# Sheet3.net
KiCad netlist of a schematic drawn in Altium Designer
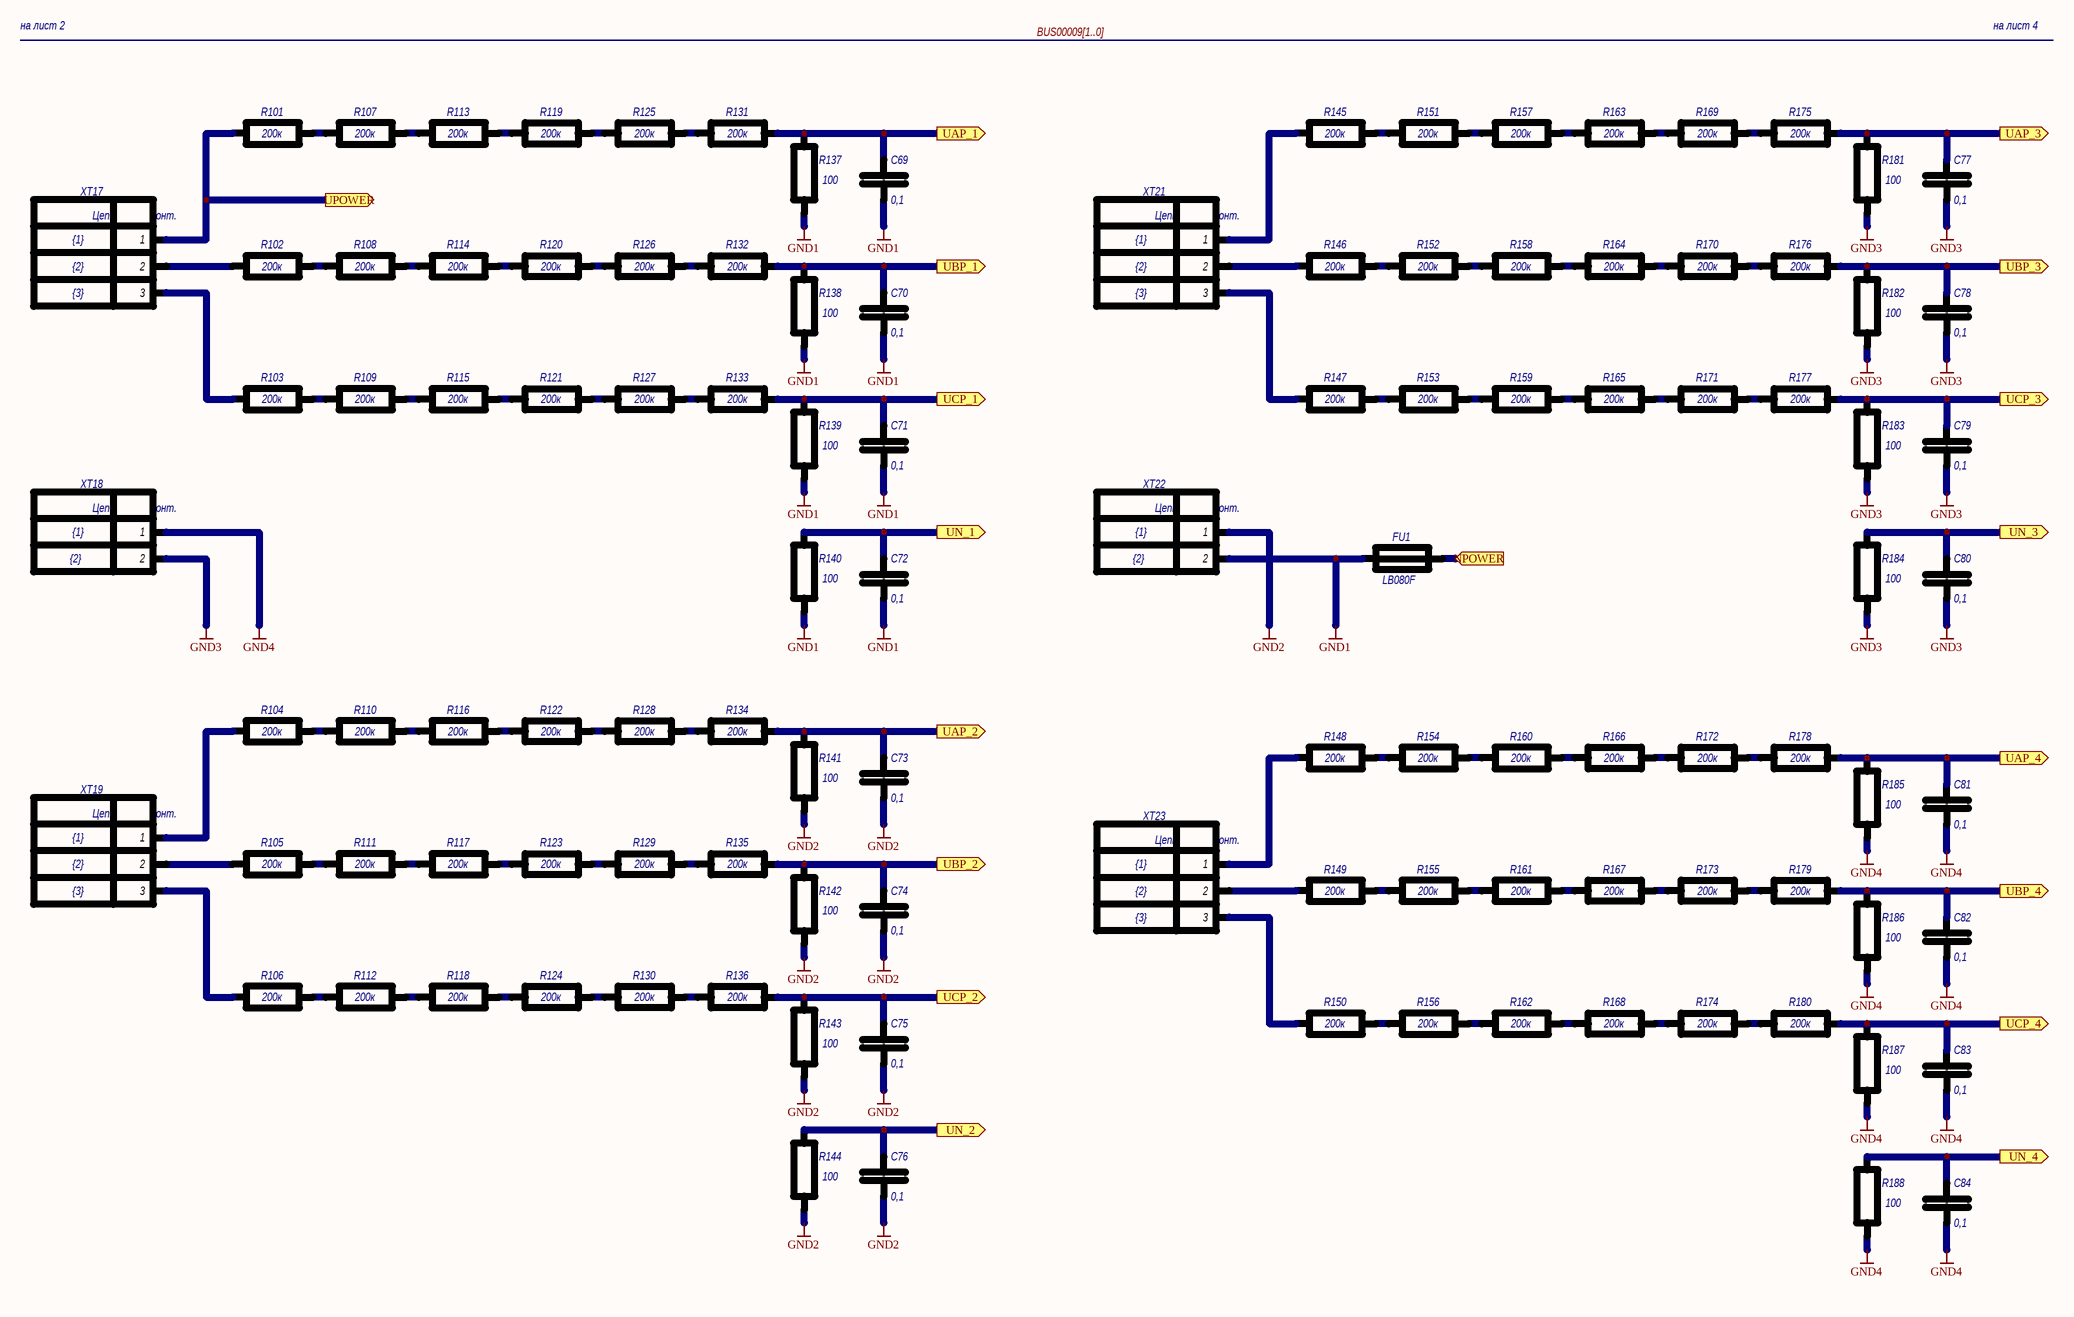
[diagram p0: Sheet3.SCHDOC]

(export (version "E")
  (design (tool "Eeschema 10.0.6"))
  (components
    (comp (ref "C69")
      (value "0,1")
      (footprint "0805")
      (description "КОНДЕНСАТОР")
      (fields (field (name "Comment") "К0805"))
      (libsource (lib "") (part "К0805_1"))
    )
    (comp (ref "C70")
      (value "0,1")
      (footprint "0805")
      (description "КОНДЕНСАТОР")
      (fields (field (name "Comment") "К0805"))
      (libsource (lib "*") (part "К0805"))
    )
    (comp (ref "C71")
      (value "0,1")
      (footprint "0805")
      (description "КОНДЕНСАТОР")
      (fields (field (name "Comment") "К0805"))
      (libsource (lib "*") (part "К0805"))
    )
    (comp (ref "C72")
      (value "0,1")
      (footprint "0805")
      (description "КОНДЕНСАТОР")
      (fields (field (name "Comment") "К0805"))
      (libsource (lib "*") (part "К0805"))
    )
    (comp (ref "C73")
      (value "0,1")
      (footprint "0805")
      (description "КОНДЕНСАТОР")
      (fields (field (name "Comment") "К0805"))
      (libsource (lib "*") (part "К0805"))
    )
    (comp (ref "C74")
      (value "0,1")
      (footprint "0805")
      (description "КОНДЕНСАТОР")
      (fields (field (name "Comment") "К0805"))
      (libsource (lib "*") (part "К0805"))
    )
    (comp (ref "C75")
      (value "0,1")
      (footprint "0805")
      (description "КОНДЕНСАТОР")
      (fields (field (name "Comment") "К0805"))
      (libsource (lib "*") (part "К0805"))
    )
    (comp (ref "C76")
      (value "0,1")
      (footprint "0805")
      (description "КОНДЕНСАТОР")
      (fields (field (name "Comment") "К0805"))
      (libsource (lib "*") (part "К0805"))
    )
    (comp (ref "C77")
      (value "0,1")
      (footprint "0805")
      (description "КОНДЕНСАТОР")
      (fields (field (name "Comment") "К0805"))
      (libsource (lib "") (part "К0805_1"))
    )
    (comp (ref "C78")
      (value "0,1")
      (footprint "0805")
      (description "КОНДЕНСАТОР")
      (fields (field (name "Comment") "К0805"))
      (libsource (lib "*") (part "К0805"))
    )
    (comp (ref "C79")
      (value "0,1")
      (footprint "0805")
      (description "КОНДЕНСАТОР")
      (fields (field (name "Comment") "К0805"))
      (libsource (lib "*") (part "К0805"))
    )
    (comp (ref "C80")
      (value "0,1")
      (footprint "0805")
      (description "КОНДЕНСАТОР")
      (fields (field (name "Comment") "К0805"))
      (libsource (lib "*") (part "К0805"))
    )
    (comp (ref "C81")
      (value "0,1")
      (footprint "0805")
      (description "КОНДЕНСАТОР")
      (fields (field (name "Comment") "К0805"))
      (libsource (lib "*") (part "К0805"))
    )
    (comp (ref "C82")
      (value "0,1")
      (footprint "0805")
      (description "КОНДЕНСАТОР")
      (fields (field (name "Comment") "К0805"))
      (libsource (lib "*") (part "К0805"))
    )
    (comp (ref "C83")
      (value "0,1")
      (footprint "0805")
      (description "КОНДЕНСАТОР")
      (fields (field (name "Comment") "К0805"))
      (libsource (lib "*") (part "К0805"))
    )
    (comp (ref "C84")
      (value "0,1")
      (footprint "0805")
      (description "КОНДЕНСАТОР")
      (fields (field (name "Comment") "К0805"))
      (libsource (lib "*") (part "К0805"))
    )
    (comp (ref "FU1")
      (value "LB080F")
      (footprint "LB080F")
      (description "{Description}")
      (libsource (lib "*") (part "LB080F"))
    )
    (comp (ref "R101")
      (value "Р1206")
      (footprint "1206")
      (description "РЕЗИСТОР")
      (fields (field (name "ALTIUM_UNNAMED_1") "200к"))
      (libsource (lib "*") (part "Р1206"))
    )
    (comp (ref "R102")
      (value "Р1206")
      (footprint "1206")
      (description "РЕЗИСТОР")
      (fields (field (name "ALTIUM_UNNAMED_1") "200к"))
      (libsource (lib "*") (part "Р1206"))
    )
    (comp (ref "R103")
      (value "Р1206")
      (footprint "1206")
      (description "РЕЗИСТОР")
      (fields (field (name "ALTIUM_UNNAMED_1") "200к"))
      (libsource (lib "*") (part "Р1206"))
    )
    (comp (ref "R104")
      (value "Р1206")
      (footprint "1206")
      (description "РЕЗИСТОР")
      (fields (field (name "ALTIUM_UNNAMED_1") "200к"))
      (libsource (lib "*") (part "Р1206"))
    )
    (comp (ref "R105")
      (value "Р1206")
      (footprint "1206")
      (description "РЕЗИСТОР")
      (fields (field (name "ALTIUM_UNNAMED_1") "200к"))
      (libsource (lib "*") (part "Р1206"))
    )
    (comp (ref "R106")
      (value "Р1206")
      (footprint "1206")
      (description "РЕЗИСТОР")
      (fields (field (name "ALTIUM_UNNAMED_1") "200к"))
      (libsource (lib "*") (part "Р1206"))
    )
    (comp (ref "R107")
      (value "Р1206")
      (footprint "1206")
      (description "РЕЗИСТОР")
      (fields (field (name "ALTIUM_UNNAMED_1") "200к"))
      (libsource (lib "") (part "Р1206_1"))
    )
    (comp (ref "R108")
      (value "Р1206")
      (footprint "1206")
      (description "РЕЗИСТОР")
      (fields (field (name "ALTIUM_UNNAMED_1") "200к"))
      (libsource (lib "") (part "Р1206_1"))
    )
    (comp (ref "R109")
      (value "Р1206")
      (footprint "1206")
      (description "РЕЗИСТОР")
      (fields (field (name "ALTIUM_UNNAMED_1") "200к"))
      (libsource (lib "") (part "Р1206_1"))
    )
    (comp (ref "R110")
      (value "Р1206")
      (footprint "1206")
      (description "РЕЗИСТОР")
      (fields (field (name "ALTIUM_UNNAMED_1") "200к"))
      (libsource (lib "") (part "Р1206_1"))
    )
    (comp (ref "R111")
      (value "Р1206")
      (footprint "1206")
      (description "РЕЗИСТОР")
      (fields (field (name "ALTIUM_UNNAMED_1") "200к"))
      (libsource (lib "") (part "Р1206_1"))
    )
    (comp (ref "R112")
      (value "Р1206")
      (footprint "1206")
      (description "РЕЗИСТОР")
      (fields (field (name "ALTIUM_UNNAMED_1") "200к"))
      (libsource (lib "") (part "Р1206_1"))
    )
    (comp (ref "R113")
      (value "Р1206")
      (footprint "1206")
      (description "РЕЗИСТОР")
      (fields (field (name "ALTIUM_UNNAMED_1") "200к"))
      (libsource (lib "*") (part "Р1206"))
    )
    (comp (ref "R114")
      (value "Р1206")
      (footprint "1206")
      (description "РЕЗИСТОР")
      (fields (field (name "ALTIUM_UNNAMED_1") "200к"))
      (libsource (lib "*") (part "Р1206"))
    )
    (comp (ref "R115")
      (value "Р1206")
      (footprint "1206")
      (description "РЕЗИСТОР")
      (fields (field (name "ALTIUM_UNNAMED_1") "200к"))
      (libsource (lib "*") (part "Р1206"))
    )
    (comp (ref "R116")
      (value "Р1206")
      (footprint "1206")
      (description "РЕЗИСТОР")
      (fields (field (name "ALTIUM_UNNAMED_1") "200к"))
      (libsource (lib "*") (part "Р1206"))
    )
    (comp (ref "R117")
      (value "Р1206")
      (footprint "1206")
      (description "РЕЗИСТОР")
      (fields (field (name "ALTIUM_UNNAMED_1") "200к"))
      (libsource (lib "*") (part "Р1206"))
    )
    (comp (ref "R118")
      (value "Р1206")
      (footprint "1206")
      (description "РЕЗИСТОР")
      (fields (field (name "ALTIUM_UNNAMED_1") "200к"))
      (libsource (lib "*") (part "Р1206"))
    )
    (comp (ref "R119")
      (value "Р1206")
      (footprint "1206")
      (description "РЕЗИСТОР")
      (fields (field (name "ALTIUM_UNNAMED_1") "200к"))
      (libsource (lib "*") (part "Р1206"))
    )
    (comp (ref "R120")
      (value "Р1206")
      (footprint "1206")
      (description "РЕЗИСТОР")
      (fields (field (name "ALTIUM_UNNAMED_1") "200к"))
      (libsource (lib "*") (part "Р1206"))
    )
    (comp (ref "R121")
      (value "Р1206")
      (footprint "1206")
      (description "РЕЗИСТОР")
      (fields (field (name "ALTIUM_UNNAMED_1") "200к"))
      (libsource (lib "*") (part "Р1206"))
    )
    (comp (ref "R122")
      (value "Р1206")
      (footprint "1206")
      (description "РЕЗИСТОР")
      (fields (field (name "ALTIUM_UNNAMED_1") "200к"))
      (libsource (lib "*") (part "Р1206"))
    )
    (comp (ref "R123")
      (value "Р1206")
      (footprint "1206")
      (description "РЕЗИСТОР")
      (fields (field (name "ALTIUM_UNNAMED_1") "200к"))
      (libsource (lib "*") (part "Р1206"))
    )
    (comp (ref "R124")
      (value "Р1206")
      (footprint "1206")
      (description "РЕЗИСТОР")
      (fields (field (name "ALTIUM_UNNAMED_1") "200к"))
      (libsource (lib "*") (part "Р1206"))
    )
    (comp (ref "R125")
      (value "Р1206")
      (footprint "1206")
      (description "РЕЗИСТОР")
      (fields (field (name "ALTIUM_UNNAMED_1") "200к"))
      (libsource (lib "*") (part "Р1206"))
    )
    (comp (ref "R126")
      (value "Р1206")
      (footprint "1206")
      (description "РЕЗИСТОР")
      (fields (field (name "ALTIUM_UNNAMED_1") "200к"))
      (libsource (lib "*") (part "Р1206"))
    )
    (comp (ref "R127")
      (value "Р1206")
      (footprint "1206")
      (description "РЕЗИСТОР")
      (fields (field (name "ALTIUM_UNNAMED_1") "200к"))
      (libsource (lib "*") (part "Р1206"))
    )
    (comp (ref "R128")
      (value "Р1206")
      (footprint "1206")
      (description "РЕЗИСТОР")
      (fields (field (name "ALTIUM_UNNAMED_1") "200к"))
      (libsource (lib "*") (part "Р1206"))
    )
    (comp (ref "R129")
      (value "Р1206")
      (footprint "1206")
      (description "РЕЗИСТОР")
      (fields (field (name "ALTIUM_UNNAMED_1") "200к"))
      (libsource (lib "*") (part "Р1206"))
    )
    (comp (ref "R130")
      (value "Р1206")
      (footprint "1206")
      (description "РЕЗИСТОР")
      (fields (field (name "ALTIUM_UNNAMED_1") "200к"))
      (libsource (lib "*") (part "Р1206"))
    )
    (comp (ref "R131")
      (value "Р1206")
      (footprint "1206")
      (description "РЕЗИСТОР")
      (fields (field (name "ALTIUM_UNNAMED_1") "200к"))
      (libsource (lib "*") (part "Р1206"))
    )
    (comp (ref "R132")
      (value "Р1206")
      (footprint "1206")
      (description "РЕЗИСТОР")
      (fields (field (name "ALTIUM_UNNAMED_1") "200к"))
      (libsource (lib "*") (part "Р1206"))
    )
    (comp (ref "R133")
      (value "Р1206")
      (footprint "1206")
      (description "РЕЗИСТОР")
      (fields (field (name "ALTIUM_UNNAMED_1") "200к"))
      (libsource (lib "*") (part "Р1206"))
    )
    (comp (ref "R134")
      (value "Р1206")
      (footprint "1206")
      (description "РЕЗИСТОР")
      (fields (field (name "ALTIUM_UNNAMED_1") "200к"))
      (libsource (lib "*") (part "Р1206"))
    )
    (comp (ref "R135")
      (value "Р1206")
      (footprint "1206")
      (description "РЕЗИСТОР")
      (fields (field (name "ALTIUM_UNNAMED_1") "200к"))
      (libsource (lib "*") (part "Р1206"))
    )
    (comp (ref "R136")
      (value "Р1206")
      (footprint "1206")
      (description "РЕЗИСТОР")
      (fields (field (name "ALTIUM_UNNAMED_1") "200к"))
      (libsource (lib "*") (part "Р1206"))
    )
    (comp (ref "R137")
      (value "100")
      (footprint "0805")
      (description "РЕЗИСТОР")
      (fields (field (name "Comment") "Р0805"))
      (libsource (lib "*") (part "Р0805"))
    )
    (comp (ref "R138")
      (value "100")
      (footprint "0805")
      (description "РЕЗИСТОР")
      (fields (field (name "Comment") "Р0805"))
      (libsource (lib "") (part "Р0805_1"))
    )
    (comp (ref "R139")
      (value "100")
      (footprint "0805")
      (description "РЕЗИСТОР")
      (fields (field (name "Comment") "Р0805"))
      (libsource (lib "") (part "Р0805_1"))
    )
    (comp (ref "R140")
      (value "100")
      (footprint "0805")
      (description "РЕЗИСТОР")
      (fields (field (name "Comment") "Р0805"))
      (libsource (lib "") (part "Р0805_1"))
    )
    (comp (ref "R141")
      (value "100")
      (footprint "0805")
      (description "РЕЗИСТОР")
      (fields (field (name "Comment") "Р0805"))
      (libsource (lib "") (part "Р0805_1"))
    )
    (comp (ref "R142")
      (value "100")
      (footprint "0805")
      (description "РЕЗИСТОР")
      (fields (field (name "Comment") "Р0805"))
      (libsource (lib "") (part "Р0805_1"))
    )
    (comp (ref "R143")
      (value "100")
      (footprint "0805")
      (description "РЕЗИСТОР")
      (fields (field (name "Comment") "Р0805"))
      (libsource (lib "") (part "Р0805_1"))
    )
    (comp (ref "R144")
      (value "100")
      (footprint "0805")
      (description "РЕЗИСТОР")
      (fields (field (name "Comment") "Р0805"))
      (libsource (lib "") (part "Р0805_1"))
    )
    (comp (ref "R145")
      (value "Р1206")
      (footprint "1206")
      (description "РЕЗИСТОР")
      (fields (field (name "ALTIUM_UNNAMED_1") "200к"))
      (libsource (lib "*") (part "Р1206"))
    )
    (comp (ref "R146")
      (value "Р1206")
      (footprint "1206")
      (description "РЕЗИСТОР")
      (fields (field (name "ALTIUM_UNNAMED_1") "200к"))
      (libsource (lib "*") (part "Р1206"))
    )
    (comp (ref "R147")
      (value "Р1206")
      (footprint "1206")
      (description "РЕЗИСТОР")
      (fields (field (name "ALTIUM_UNNAMED_1") "200к"))
      (libsource (lib "*") (part "Р1206"))
    )
    (comp (ref "R148")
      (value "Р1206")
      (footprint "1206")
      (description "РЕЗИСТОР")
      (fields (field (name "ALTIUM_UNNAMED_1") "200к"))
      (libsource (lib "*") (part "Р1206"))
    )
    (comp (ref "R149")
      (value "Р1206")
      (footprint "1206")
      (description "РЕЗИСТОР")
      (fields (field (name "ALTIUM_UNNAMED_1") "200к"))
      (libsource (lib "*") (part "Р1206"))
    )
    (comp (ref "R150")
      (value "Р1206")
      (footprint "1206")
      (description "РЕЗИСТОР")
      (fields (field (name "ALTIUM_UNNAMED_1") "200к"))
      (libsource (lib "*") (part "Р1206"))
    )
    (comp (ref "R151")
      (value "Р1206")
      (footprint "1206")
      (description "РЕЗИСТОР")
      (fields (field (name "ALTIUM_UNNAMED_1") "200к"))
      (libsource (lib "*") (part "Р1206"))
    )
    (comp (ref "R152")
      (value "Р1206")
      (footprint "1206")
      (description "РЕЗИСТОР")
      (fields (field (name "ALTIUM_UNNAMED_1") "200к"))
      (libsource (lib "*") (part "Р1206"))
    )
    (comp (ref "R153")
      (value "Р1206")
      (footprint "1206")
      (description "РЕЗИСТОР")
      (fields (field (name "ALTIUM_UNNAMED_1") "200к"))
      (libsource (lib "*") (part "Р1206"))
    )
    (comp (ref "R154")
      (value "Р1206")
      (footprint "1206")
      (description "РЕЗИСТОР")
      (fields (field (name "ALTIUM_UNNAMED_1") "200к"))
      (libsource (lib "*") (part "Р1206"))
    )
    (comp (ref "R155")
      (value "Р1206")
      (footprint "1206")
      (description "РЕЗИСТОР")
      (fields (field (name "ALTIUM_UNNAMED_1") "200к"))
      (libsource (lib "*") (part "Р1206"))
    )
    (comp (ref "R156")
      (value "Р1206")
      (footprint "1206")
      (description "РЕЗИСТОР")
      (fields (field (name "ALTIUM_UNNAMED_1") "200к"))
      (libsource (lib "*") (part "Р1206"))
    )
    (comp (ref "R157")
      (value "Р1206")
      (footprint "1206")
      (description "РЕЗИСТОР")
      (fields (field (name "ALTIUM_UNNAMED_1") "200к"))
      (libsource (lib "*") (part "Р1206"))
    )
    (comp (ref "R158")
      (value "Р1206")
      (footprint "1206")
      (description "РЕЗИСТОР")
      (fields (field (name "ALTIUM_UNNAMED_1") "200к"))
      (libsource (lib "*") (part "Р1206"))
    )
    (comp (ref "R159")
      (value "Р1206")
      (footprint "1206")
      (description "РЕЗИСТОР")
      (fields (field (name "ALTIUM_UNNAMED_1") "200к"))
      (libsource (lib "*") (part "Р1206"))
    )
    (comp (ref "R160")
      (value "Р1206")
      (footprint "1206")
      (description "РЕЗИСТОР")
      (fields (field (name "ALTIUM_UNNAMED_1") "200к"))
      (libsource (lib "*") (part "Р1206"))
    )
    (comp (ref "R161")
      (value "Р1206")
      (footprint "1206")
      (description "РЕЗИСТОР")
      (fields (field (name "ALTIUM_UNNAMED_1") "200к"))
      (libsource (lib "*") (part "Р1206"))
    )
    (comp (ref "R162")
      (value "Р1206")
      (footprint "1206")
      (description "РЕЗИСТОР")
      (fields (field (name "ALTIUM_UNNAMED_1") "200к"))
      (libsource (lib "*") (part "Р1206"))
    )
    (comp (ref "R163")
      (value "Р1206")
      (footprint "1206")
      (description "РЕЗИСТОР")
      (fields (field (name "ALTIUM_UNNAMED_1") "200к"))
      (libsource (lib "*") (part "Р1206"))
    )
    (comp (ref "R164")
      (value "Р1206")
      (footprint "1206")
      (description "РЕЗИСТОР")
      (fields (field (name "ALTIUM_UNNAMED_1") "200к"))
      (libsource (lib "*") (part "Р1206"))
    )
    (comp (ref "R165")
      (value "Р1206")
      (footprint "1206")
      (description "РЕЗИСТОР")
      (fields (field (name "ALTIUM_UNNAMED_1") "200к"))
      (libsource (lib "*") (part "Р1206"))
    )
    (comp (ref "R166")
      (value "Р1206")
      (footprint "1206")
      (description "РЕЗИСТОР")
      (fields (field (name "ALTIUM_UNNAMED_1") "200к"))
      (libsource (lib "*") (part "Р1206"))
    )
    (comp (ref "R167")
      (value "Р1206")
      (footprint "1206")
      (description "РЕЗИСТОР")
      (fields (field (name "ALTIUM_UNNAMED_1") "200к"))
      (libsource (lib "*") (part "Р1206"))
    )
    (comp (ref "R168")
      (value "Р1206")
      (footprint "1206")
      (description "РЕЗИСТОР")
      (fields (field (name "ALTIUM_UNNAMED_1") "200к"))
      (libsource (lib "*") (part "Р1206"))
    )
    (comp (ref "R169")
      (value "Р1206")
      (footprint "1206")
      (description "РЕЗИСТОР")
      (fields (field (name "ALTIUM_UNNAMED_1") "200к"))
      (libsource (lib "*") (part "Р1206"))
    )
    (comp (ref "R170")
      (value "Р1206")
      (footprint "1206")
      (description "РЕЗИСТОР")
      (fields (field (name "ALTIUM_UNNAMED_1") "200к"))
      (libsource (lib "*") (part "Р1206"))
    )
    (comp (ref "R171")
      (value "Р1206")
      (footprint "1206")
      (description "РЕЗИСТОР")
      (fields (field (name "ALTIUM_UNNAMED_1") "200к"))
      (libsource (lib "*") (part "Р1206"))
    )
    (comp (ref "R172")
      (value "Р1206")
      (footprint "1206")
      (description "РЕЗИСТОР")
      (fields (field (name "ALTIUM_UNNAMED_1") "200к"))
      (libsource (lib "*") (part "Р1206"))
    )
    (comp (ref "R173")
      (value "Р1206")
      (footprint "1206")
      (description "РЕЗИСТОР")
      (fields (field (name "ALTIUM_UNNAMED_1") "200к"))
      (libsource (lib "*") (part "Р1206"))
    )
    (comp (ref "R174")
      (value "Р1206")
      (footprint "1206")
      (description "РЕЗИСТОР")
      (fields (field (name "ALTIUM_UNNAMED_1") "200к"))
      (libsource (lib "*") (part "Р1206"))
    )
    (comp (ref "R175")
      (value "Р1206")
      (footprint "1206")
      (description "РЕЗИСТОР")
      (fields (field (name "ALTIUM_UNNAMED_1") "200к"))
      (libsource (lib "*") (part "Р1206"))
    )
    (comp (ref "R176")
      (value "Р1206")
      (footprint "1206")
      (description "РЕЗИСТОР")
      (fields (field (name "ALTIUM_UNNAMED_1") "200к"))
      (libsource (lib "*") (part "Р1206"))
    )
    (comp (ref "R177")
      (value "Р1206")
      (footprint "1206")
      (description "РЕЗИСТОР")
      (fields (field (name "ALTIUM_UNNAMED_1") "200к"))
      (libsource (lib "*") (part "Р1206"))
    )
    (comp (ref "R178")
      (value "Р1206")
      (footprint "1206")
      (description "РЕЗИСТОР")
      (fields (field (name "ALTIUM_UNNAMED_1") "200к"))
      (libsource (lib "*") (part "Р1206"))
    )
    (comp (ref "R179")
      (value "Р1206")
      (footprint "1206")
      (description "РЕЗИСТОР")
      (fields (field (name "ALTIUM_UNNAMED_1") "200к"))
      (libsource (lib "*") (part "Р1206"))
    )
    (comp (ref "R180")
      (value "Р1206")
      (footprint "1206")
      (description "РЕЗИСТОР")
      (fields (field (name "ALTIUM_UNNAMED_1") "200к"))
      (libsource (lib "*") (part "Р1206"))
    )
    (comp (ref "R181")
      (value "100")
      (footprint "0805")
      (description "РЕЗИСТОР")
      (fields (field (name "Comment") "Р0805"))
      (libsource (lib "*") (part "Р0805"))
    )
    (comp (ref "R182")
      (value "100")
      (footprint "0805")
      (description "РЕЗИСТОР")
      (fields (field (name "Comment") "Р0805"))
      (libsource (lib "") (part "Р0805_1"))
    )
    (comp (ref "R183")
      (value "100")
      (footprint "0805")
      (description "РЕЗИСТОР")
      (fields (field (name "Comment") "Р0805"))
      (libsource (lib "") (part "Р0805_1"))
    )
    (comp (ref "R184")
      (value "100")
      (footprint "0805")
      (description "РЕЗИСТОР")
      (fields (field (name "Comment") "Р0805"))
      (libsource (lib "") (part "Р0805_1"))
    )
    (comp (ref "R185")
      (value "100")
      (footprint "0805")
      (description "РЕЗИСТОР")
      (fields (field (name "Comment") "Р0805"))
      (libsource (lib "") (part "Р0805_1"))
    )
    (comp (ref "R186")
      (value "100")
      (footprint "0805")
      (description "РЕЗИСТОР")
      (fields (field (name "Comment") "Р0805"))
      (libsource (lib "") (part "Р0805_1"))
    )
    (comp (ref "R187")
      (value "100")
      (footprint "0805")
      (description "РЕЗИСТОР")
      (fields (field (name "Comment") "Р0805"))
      (libsource (lib "") (part "Р0805_1"))
    )
    (comp (ref "R188")
      (value "100")
      (footprint "0805")
      (description "РЕЗИСТОР")
      (fields (field (name "Comment") "Р0805"))
      (libsource (lib "") (part "Р0805_1"))
    )
    (comp (ref "XT17")
      (value "EK508V-03P")
      (footprint "EK508V-03P")
      (description "{Description}")
      (fields (field (name "2") "{2}") (field (name "1") "{1}") (field (name "3") "{3}"))
      (libsource (lib "*") (part "EK508V-03P"))
    )
    (comp (ref "XT18")
      (value "EK508V-02P")
      (footprint "EK508V-02P")
      (description "{Description}")
      (fields (field (name "2") "{2}") (field (name "1") "{1}"))
      (libsource (lib "*") (part "EK508V-02P"))
    )
    (comp (ref "XT19")
      (value "EK508V-03P")
      (footprint "EK508V-03P")
      (description "{Description}")
      (fields (field (name "2") "{2}") (field (name "1") "{1}") (field (name "3") "{3}"))
      (libsource (lib "*") (part "EK508V-03P"))
    )
    (comp (ref "XT21")
      (value "EK508V-03P")
      (footprint "EK508V-03P")
      (description "{Description}")
      (fields (field (name "2") "{2}") (field (name "1") "{1}") (field (name "3") "{3}"))
      (libsource (lib "*") (part "EK508V-03P"))
    )
    (comp (ref "XT22")
      (value "EK508V-02P")
      (footprint "EK508V-02P")
      (description "{Description}")
      (fields (field (name "2") "{2}") (field (name "1") "{1}"))
      (libsource (lib "*") (part "EK508V-02P"))
    )
    (comp (ref "XT23")
      (value "EK508V-03P")
      (footprint "EK508V-03P")
      (description "{Description}")
      (fields (field (name "2") "{2}") (field (name "1") "{1}") (field (name "3") "{3}"))
      (libsource (lib "*") (part "EK508V-03P"))
    )
  )
  (nets
    (net (code "4") (name "/NPOWER") (class "Default")
      (node (ref "FU1") (pin "2") (pinfunction "2_2") (pintype "passive"))
    )
    (net (code "5") (name "/UAP_1") (class "Default")
      (node (ref "C69") (pin "2") (pinfunction "2_2") (pintype "passive"))
      (node (ref "R131") (pin "1") (pinfunction "1_1") (pintype "passive"))
      (node (ref "R137") (pin "2") (pinfunction "2_2") (pintype "passive"))
    )
    (net (code "6") (name "/UAP_2") (class "Default")
      (node (ref "C73") (pin "2") (pinfunction "2_2") (pintype "passive"))
      (node (ref "R134") (pin "1") (pinfunction "1_1") (pintype "passive"))
      (node (ref "R141") (pin "2") (pinfunction "2_2") (pintype "passive"))
    )
    (net (code "7") (name "/UAP_3") (class "Default")
      (node (ref "C77") (pin "2") (pinfunction "2_2") (pintype "passive"))
      (node (ref "R175") (pin "1") (pinfunction "1_1") (pintype "passive"))
      (node (ref "R181") (pin "2") (pinfunction "2_2") (pintype "passive"))
    )
    (net (code "8") (name "/UAP_4") (class "Default")
      (node (ref "C81") (pin "2") (pinfunction "2_2") (pintype "passive"))
      (node (ref "R178") (pin "1") (pinfunction "1_1") (pintype "passive"))
      (node (ref "R185") (pin "2") (pinfunction "2_2") (pintype "passive"))
    )
    (net (code "9") (name "/UBP_1") (class "Default")
      (node (ref "C70") (pin "2") (pinfunction "2_2") (pintype "passive"))
      (node (ref "R132") (pin "1") (pinfunction "1_1") (pintype "passive"))
      (node (ref "R138") (pin "2") (pinfunction "2_2") (pintype "passive"))
    )
    (net (code "10") (name "/UBP_2") (class "Default")
      (node (ref "C74") (pin "2") (pinfunction "2_2") (pintype "passive"))
      (node (ref "R135") (pin "1") (pinfunction "1_1") (pintype "passive"))
      (node (ref "R142") (pin "2") (pinfunction "2_2") (pintype "passive"))
    )
    (net (code "11") (name "/UBP_3") (class "Default")
      (node (ref "C78") (pin "2") (pinfunction "2_2") (pintype "passive"))
      (node (ref "R176") (pin "1") (pinfunction "1_1") (pintype "passive"))
      (node (ref "R182") (pin "2") (pinfunction "2_2") (pintype "passive"))
    )
    (net (code "12") (name "/UBP_4") (class "Default")
      (node (ref "C82") (pin "2") (pinfunction "2_2") (pintype "passive"))
      (node (ref "R179") (pin "1") (pinfunction "1_1") (pintype "passive"))
      (node (ref "R186") (pin "2") (pinfunction "2_2") (pintype "passive"))
    )
    (net (code "13") (name "/UCP_1") (class "Default")
      (node (ref "C71") (pin "2") (pinfunction "2_2") (pintype "passive"))
      (node (ref "R133") (pin "1") (pinfunction "1_1") (pintype "passive"))
      (node (ref "R139") (pin "2") (pinfunction "2_2") (pintype "passive"))
    )
    (net (code "14") (name "/UCP_2") (class "Default")
      (node (ref "C75") (pin "2") (pinfunction "2_2") (pintype "passive"))
      (node (ref "R136") (pin "1") (pinfunction "1_1") (pintype "passive"))
      (node (ref "R143") (pin "2") (pinfunction "2_2") (pintype "passive"))
    )
    (net (code "15") (name "/UCP_3") (class "Default")
      (node (ref "C79") (pin "2") (pinfunction "2_2") (pintype "passive"))
      (node (ref "R177") (pin "1") (pinfunction "1_1") (pintype "passive"))
      (node (ref "R183") (pin "2") (pinfunction "2_2") (pintype "passive"))
    )
    (net (code "16") (name "/UCP_4") (class "Default")
      (node (ref "C83") (pin "2") (pinfunction "2_2") (pintype "passive"))
      (node (ref "R180") (pin "1") (pinfunction "1_1") (pintype "passive"))
      (node (ref "R187") (pin "2") (pinfunction "2_2") (pintype "passive"))
    )
    (net (code "17") (name "/UN_1") (class "Default")
      (node (ref "C72") (pin "2") (pinfunction "2_2") (pintype "passive"))
      (node (ref "R140") (pin "2") (pinfunction "2_2") (pintype "passive"))
    )
    (net (code "18") (name "/UN_2") (class "Default")
      (node (ref "C76") (pin "2") (pinfunction "2_2") (pintype "passive"))
      (node (ref "R144") (pin "2") (pinfunction "2_2") (pintype "passive"))
    )
    (net (code "19") (name "/UN_3") (class "Default")
      (node (ref "C80") (pin "2") (pinfunction "2_2") (pintype "passive"))
      (node (ref "R184") (pin "2") (pinfunction "2_2") (pintype "passive"))
    )
    (net (code "20") (name "/UN_4") (class "Default")
      (node (ref "C84") (pin "2") (pinfunction "2_2") (pintype "passive"))
      (node (ref "R188") (pin "2") (pinfunction "2_2") (pintype "passive"))
    )
    (net (code "21") (name "/UPOWER") (class "Default")
      (node (ref "R101") (pin "1") (pinfunction "1_1") (pintype "passive"))
      (node (ref "XT17") (pin "1") (pinfunction "1_1") (pintype "passive"))
    )
    (net (code "22") (name "GND1") (class "Default")
      (node (ref "C69") (pin "1") (pinfunction "1_1") (pintype "passive"))
      (node (ref "C70") (pin "1") (pinfunction "1_1") (pintype "passive"))
      (node (ref "C71") (pin "1") (pinfunction "1_1") (pintype "passive"))
      (node (ref "C72") (pin "1") (pinfunction "1_1") (pintype "passive"))
      (node (ref "FU1") (pin "1") (pinfunction "1_1") (pintype "passive"))
      (node (ref "R137") (pin "1") (pinfunction "1_1") (pintype "passive"))
      (node (ref "R138") (pin "1") (pinfunction "1_1") (pintype "passive"))
      (node (ref "R139") (pin "1") (pinfunction "1_1") (pintype "passive"))
      (node (ref "R140") (pin "1") (pinfunction "1_1") (pintype "passive"))
      (node (ref "XT22") (pin "2") (pinfunction "2_2") (pintype "passive"))
    )
    (net (code "23") (name "GND2") (class "Default")
      (node (ref "C73") (pin "1") (pinfunction "1_1") (pintype "passive"))
      (node (ref "C74") (pin "1") (pinfunction "1_1") (pintype "passive"))
      (node (ref "C75") (pin "1") (pinfunction "1_1") (pintype "passive"))
      (node (ref "C76") (pin "1") (pinfunction "1_1") (pintype "passive"))
      (node (ref "R141") (pin "1") (pinfunction "1_1") (pintype "passive"))
      (node (ref "R142") (pin "1") (pinfunction "1_1") (pintype "passive"))
      (node (ref "R143") (pin "1") (pinfunction "1_1") (pintype "passive"))
      (node (ref "R144") (pin "1") (pinfunction "1_1") (pintype "passive"))
      (node (ref "XT22") (pin "1") (pinfunction "1_1") (pintype "passive"))
    )
    (net (code "24") (name "GND3") (class "Default")
      (node (ref "C77") (pin "1") (pinfunction "1_1") (pintype "passive"))
      (node (ref "C78") (pin "1") (pinfunction "1_1") (pintype "passive"))
      (node (ref "C79") (pin "1") (pinfunction "1_1") (pintype "passive"))
      (node (ref "C80") (pin "1") (pinfunction "1_1") (pintype "passive"))
      (node (ref "R181") (pin "1") (pinfunction "1_1") (pintype "passive"))
      (node (ref "R182") (pin "1") (pinfunction "1_1") (pintype "passive"))
      (node (ref "R183") (pin "1") (pinfunction "1_1") (pintype "passive"))
      (node (ref "R184") (pin "1") (pinfunction "1_1") (pintype "passive"))
      (node (ref "XT18") (pin "2") (pinfunction "2_2") (pintype "passive"))
    )
    (net (code "25") (name "GND4") (class "Default")
      (node (ref "C81") (pin "1") (pinfunction "1_1") (pintype "passive"))
      (node (ref "C82") (pin "1") (pinfunction "1_1") (pintype "passive"))
      (node (ref "C83") (pin "1") (pinfunction "1_1") (pintype "passive"))
      (node (ref "C84") (pin "1") (pinfunction "1_1") (pintype "passive"))
      (node (ref "R185") (pin "1") (pinfunction "1_1") (pintype "passive"))
      (node (ref "R186") (pin "1") (pinfunction "1_1") (pintype "passive"))
      (node (ref "R187") (pin "1") (pinfunction "1_1") (pintype "passive"))
      (node (ref "R188") (pin "1") (pinfunction "1_1") (pintype "passive"))
      (node (ref "XT18") (pin "1") (pinfunction "1_1") (pintype "passive"))
    )
    (net (code "26") (name "Net-(R101-Pad2)") (class "Default")
      (node (ref "R101") (pin "2") (pinfunction "2_2") (pintype "passive"))
      (node (ref "R107") (pin "1") (pinfunction "1_1") (pintype "passive"))
    )
    (net (code "27") (name "Net-(R102-Pad1)") (class "Default")
      (node (ref "R102") (pin "1") (pinfunction "1_1") (pintype "passive"))
      (node (ref "XT17") (pin "2") (pinfunction "2_2") (pintype "passive"))
    )
    (net (code "28") (name "Net-(R102-Pad2)") (class "Default")
      (node (ref "R102") (pin "2") (pinfunction "2_2") (pintype "passive"))
      (node (ref "R108") (pin "1") (pinfunction "1_1") (pintype "passive"))
    )
    (net (code "29") (name "Net-(R103-Pad1)") (class "Default")
      (node (ref "R103") (pin "1") (pinfunction "1_1") (pintype "passive"))
      (node (ref "XT17") (pin "3") (pinfunction "3_3") (pintype "passive"))
    )
    (net (code "30") (name "Net-(R103-Pad2)") (class "Default")
      (node (ref "R103") (pin "2") (pinfunction "2_2") (pintype "passive"))
      (node (ref "R109") (pin "1") (pinfunction "1_1") (pintype "passive"))
    )
    (net (code "31") (name "Net-(R104-Pad1)") (class "Default")
      (node (ref "R104") (pin "1") (pinfunction "1_1") (pintype "passive"))
      (node (ref "XT19") (pin "1") (pinfunction "1_1") (pintype "passive"))
    )
    (net (code "32") (name "Net-(R104-Pad2)") (class "Default")
      (node (ref "R104") (pin "2") (pinfunction "2_2") (pintype "passive"))
      (node (ref "R110") (pin "1") (pinfunction "1_1") (pintype "passive"))
    )
    (net (code "33") (name "Net-(R105-Pad1)") (class "Default")
      (node (ref "R105") (pin "1") (pinfunction "1_1") (pintype "passive"))
      (node (ref "XT19") (pin "2") (pinfunction "2_2") (pintype "passive"))
    )
    (net (code "34") (name "Net-(R105-Pad2)") (class "Default")
      (node (ref "R105") (pin "2") (pinfunction "2_2") (pintype "passive"))
      (node (ref "R111") (pin "1") (pinfunction "1_1") (pintype "passive"))
    )
    (net (code "35") (name "Net-(R106-Pad1)") (class "Default")
      (node (ref "R106") (pin "1") (pinfunction "1_1") (pintype "passive"))
      (node (ref "XT19") (pin "3") (pinfunction "3_3") (pintype "passive"))
    )
    (net (code "36") (name "Net-(R106-Pad2)") (class "Default")
      (node (ref "R106") (pin "2") (pinfunction "2_2") (pintype "passive"))
      (node (ref "R112") (pin "1") (pinfunction "1_1") (pintype "passive"))
    )
    (net (code "37") (name "Net-(R107-Pad2)") (class "Default")
      (node (ref "R107") (pin "2") (pinfunction "2_2") (pintype "passive"))
      (node (ref "R113") (pin "1") (pinfunction "1_1") (pintype "passive"))
    )
    (net (code "38") (name "Net-(R108-Pad2)") (class "Default")
      (node (ref "R108") (pin "2") (pinfunction "2_2") (pintype "passive"))
      (node (ref "R114") (pin "1") (pinfunction "1_1") (pintype "passive"))
    )
    (net (code "39") (name "Net-(R109-Pad2)") (class "Default")
      (node (ref "R109") (pin "2") (pinfunction "2_2") (pintype "passive"))
      (node (ref "R115") (pin "1") (pinfunction "1_1") (pintype "passive"))
    )
    (net (code "40") (name "Net-(R110-Pad2)") (class "Default")
      (node (ref "R110") (pin "2") (pinfunction "2_2") (pintype "passive"))
      (node (ref "R116") (pin "1") (pinfunction "1_1") (pintype "passive"))
    )
    (net (code "41") (name "Net-(R111-Pad2)") (class "Default")
      (node (ref "R111") (pin "2") (pinfunction "2_2") (pintype "passive"))
      (node (ref "R117") (pin "1") (pinfunction "1_1") (pintype "passive"))
    )
    (net (code "42") (name "Net-(R112-Pad2)") (class "Default")
      (node (ref "R112") (pin "2") (pinfunction "2_2") (pintype "passive"))
      (node (ref "R118") (pin "1") (pinfunction "1_1") (pintype "passive"))
    )
    (net (code "43") (name "Net-(R113-Pad2)") (class "Default")
      (node (ref "R113") (pin "2") (pinfunction "2_2") (pintype "passive"))
      (node (ref "R119") (pin "2") (pinfunction "2_2") (pintype "passive"))
    )
    (net (code "44") (name "Net-(R114-Pad2)") (class "Default")
      (node (ref "R114") (pin "2") (pinfunction "2_2") (pintype "passive"))
      (node (ref "R120") (pin "2") (pinfunction "2_2") (pintype "passive"))
    )
    (net (code "45") (name "Net-(R115-Pad2)") (class "Default")
      (node (ref "R115") (pin "2") (pinfunction "2_2") (pintype "passive"))
      (node (ref "R121") (pin "2") (pinfunction "2_2") (pintype "passive"))
    )
    (net (code "46") (name "Net-(R116-Pad2)") (class "Default")
      (node (ref "R116") (pin "2") (pinfunction "2_2") (pintype "passive"))
      (node (ref "R122") (pin "2") (pinfunction "2_2") (pintype "passive"))
    )
    (net (code "47") (name "Net-(R117-Pad2)") (class "Default")
      (node (ref "R117") (pin "2") (pinfunction "2_2") (pintype "passive"))
      (node (ref "R123") (pin "2") (pinfunction "2_2") (pintype "passive"))
    )
    (net (code "48") (name "Net-(R118-Pad2)") (class "Default")
      (node (ref "R118") (pin "2") (pinfunction "2_2") (pintype "passive"))
      (node (ref "R124") (pin "2") (pinfunction "2_2") (pintype "passive"))
    )
    (net (code "49") (name "Net-(R119-Pad1)") (class "Default")
      (node (ref "R119") (pin "1") (pinfunction "1_1") (pintype "passive"))
      (node (ref "R125") (pin "2") (pinfunction "2_2") (pintype "passive"))
    )
    (net (code "50") (name "Net-(R120-Pad1)") (class "Default")
      (node (ref "R120") (pin "1") (pinfunction "1_1") (pintype "passive"))
      (node (ref "R126") (pin "2") (pinfunction "2_2") (pintype "passive"))
    )
    (net (code "51") (name "Net-(R121-Pad1)") (class "Default")
      (node (ref "R121") (pin "1") (pinfunction "1_1") (pintype "passive"))
      (node (ref "R127") (pin "2") (pinfunction "2_2") (pintype "passive"))
    )
    (net (code "52") (name "Net-(R122-Pad1)") (class "Default")
      (node (ref "R122") (pin "1") (pinfunction "1_1") (pintype "passive"))
      (node (ref "R128") (pin "2") (pinfunction "2_2") (pintype "passive"))
    )
    (net (code "53") (name "Net-(R123-Pad1)") (class "Default")
      (node (ref "R123") (pin "1") (pinfunction "1_1") (pintype "passive"))
      (node (ref "R129") (pin "2") (pinfunction "2_2") (pintype "passive"))
    )
    (net (code "54") (name "Net-(R124-Pad1)") (class "Default")
      (node (ref "R124") (pin "1") (pinfunction "1_1") (pintype "passive"))
      (node (ref "R130") (pin "2") (pinfunction "2_2") (pintype "passive"))
    )
    (net (code "55") (name "Net-(R125-Pad1)") (class "Default")
      (node (ref "R125") (pin "1") (pinfunction "1_1") (pintype "passive"))
      (node (ref "R131") (pin "2") (pinfunction "2_2") (pintype "passive"))
    )
    (net (code "56") (name "Net-(R126-Pad1)") (class "Default")
      (node (ref "R126") (pin "1") (pinfunction "1_1") (pintype "passive"))
      (node (ref "R132") (pin "2") (pinfunction "2_2") (pintype "passive"))
    )
    (net (code "57") (name "Net-(R127-Pad1)") (class "Default")
      (node (ref "R127") (pin "1") (pinfunction "1_1") (pintype "passive"))
      (node (ref "R133") (pin "2") (pinfunction "2_2") (pintype "passive"))
    )
    (net (code "58") (name "Net-(R128-Pad1)") (class "Default")
      (node (ref "R128") (pin "1") (pinfunction "1_1") (pintype "passive"))
      (node (ref "R134") (pin "2") (pinfunction "2_2") (pintype "passive"))
    )
    (net (code "59") (name "Net-(R129-Pad1)") (class "Default")
      (node (ref "R129") (pin "1") (pinfunction "1_1") (pintype "passive"))
      (node (ref "R135") (pin "2") (pinfunction "2_2") (pintype "passive"))
    )
    (net (code "60") (name "Net-(R130-Pad1)") (class "Default")
      (node (ref "R130") (pin "1") (pinfunction "1_1") (pintype "passive"))
      (node (ref "R136") (pin "2") (pinfunction "2_2") (pintype "passive"))
    )
    (net (code "61") (name "Net-(R145-Pad1)") (class "Default")
      (node (ref "R145") (pin "1") (pinfunction "1_1") (pintype "passive"))
      (node (ref "XT21") (pin "1") (pinfunction "1_1") (pintype "passive"))
    )
    (net (code "62") (name "Net-(R145-Pad2)") (class "Default")
      (node (ref "R145") (pin "2") (pinfunction "2_2") (pintype "passive"))
      (node (ref "R151") (pin "1") (pinfunction "1_1") (pintype "passive"))
    )
    (net (code "63") (name "Net-(R146-Pad1)") (class "Default")
      (node (ref "R146") (pin "1") (pinfunction "1_1") (pintype "passive"))
      (node (ref "XT21") (pin "2") (pinfunction "2_2") (pintype "passive"))
    )
    (net (code "64") (name "Net-(R146-Pad2)") (class "Default")
      (node (ref "R146") (pin "2") (pinfunction "2_2") (pintype "passive"))
      (node (ref "R152") (pin "1") (pinfunction "1_1") (pintype "passive"))
    )
    (net (code "65") (name "Net-(R147-Pad1)") (class "Default")
      (node (ref "R147") (pin "1") (pinfunction "1_1") (pintype "passive"))
      (node (ref "XT21") (pin "3") (pinfunction "3_3") (pintype "passive"))
    )
    (net (code "66") (name "Net-(R147-Pad2)") (class "Default")
      (node (ref "R147") (pin "2") (pinfunction "2_2") (pintype "passive"))
      (node (ref "R153") (pin "1") (pinfunction "1_1") (pintype "passive"))
    )
    (net (code "67") (name "Net-(R148-Pad1)") (class "Default")
      (node (ref "R148") (pin "1") (pinfunction "1_1") (pintype "passive"))
      (node (ref "XT23") (pin "1") (pinfunction "1_1") (pintype "passive"))
    )
    (net (code "68") (name "Net-(R148-Pad2)") (class "Default")
      (node (ref "R148") (pin "2") (pinfunction "2_2") (pintype "passive"))
      (node (ref "R154") (pin "1") (pinfunction "1_1") (pintype "passive"))
    )
    (net (code "69") (name "Net-(R149-Pad1)") (class "Default")
      (node (ref "R149") (pin "1") (pinfunction "1_1") (pintype "passive"))
      (node (ref "XT23") (pin "2") (pinfunction "2_2") (pintype "passive"))
    )
    (net (code "70") (name "Net-(R149-Pad2)") (class "Default")
      (node (ref "R149") (pin "2") (pinfunction "2_2") (pintype "passive"))
      (node (ref "R155") (pin "1") (pinfunction "1_1") (pintype "passive"))
    )
    (net (code "71") (name "Net-(R150-Pad1)") (class "Default")
      (node (ref "R150") (pin "1") (pinfunction "1_1") (pintype "passive"))
      (node (ref "XT23") (pin "3") (pinfunction "3_3") (pintype "passive"))
    )
    (net (code "72") (name "Net-(R150-Pad2)") (class "Default")
      (node (ref "R150") (pin "2") (pinfunction "2_2") (pintype "passive"))
      (node (ref "R156") (pin "1") (pinfunction "1_1") (pintype "passive"))
    )
    (net (code "73") (name "Net-(R151-Pad2)") (class "Default")
      (node (ref "R151") (pin "2") (pinfunction "2_2") (pintype "passive"))
      (node (ref "R157") (pin "1") (pinfunction "1_1") (pintype "passive"))
    )
    (net (code "74") (name "Net-(R152-Pad2)") (class "Default")
      (node (ref "R152") (pin "2") (pinfunction "2_2") (pintype "passive"))
      (node (ref "R158") (pin "1") (pinfunction "1_1") (pintype "passive"))
    )
    (net (code "75") (name "Net-(R153-Pad2)") (class "Default")
      (node (ref "R153") (pin "2") (pinfunction "2_2") (pintype "passive"))
      (node (ref "R159") (pin "1") (pinfunction "1_1") (pintype "passive"))
    )
    (net (code "76") (name "Net-(R154-Pad2)") (class "Default")
      (node (ref "R154") (pin "2") (pinfunction "2_2") (pintype "passive"))
      (node (ref "R160") (pin "1") (pinfunction "1_1") (pintype "passive"))
    )
    (net (code "77") (name "Net-(R155-Pad2)") (class "Default")
      (node (ref "R155") (pin "2") (pinfunction "2_2") (pintype "passive"))
      (node (ref "R161") (pin "1") (pinfunction "1_1") (pintype "passive"))
    )
    (net (code "78") (name "Net-(R156-Pad2)") (class "Default")
      (node (ref "R156") (pin "2") (pinfunction "2_2") (pintype "passive"))
      (node (ref "R162") (pin "1") (pinfunction "1_1") (pintype "passive"))
    )
    (net (code "79") (name "Net-(R157-Pad2)") (class "Default")
      (node (ref "R157") (pin "2") (pinfunction "2_2") (pintype "passive"))
      (node (ref "R163") (pin "2") (pinfunction "2_2") (pintype "passive"))
    )
    (net (code "80") (name "Net-(R158-Pad2)") (class "Default")
      (node (ref "R158") (pin "2") (pinfunction "2_2") (pintype "passive"))
      (node (ref "R164") (pin "2") (pinfunction "2_2") (pintype "passive"))
    )
    (net (code "81") (name "Net-(R159-Pad2)") (class "Default")
      (node (ref "R159") (pin "2") (pinfunction "2_2") (pintype "passive"))
      (node (ref "R165") (pin "2") (pinfunction "2_2") (pintype "passive"))
    )
    (net (code "82") (name "Net-(R160-Pad2)") (class "Default")
      (node (ref "R160") (pin "2") (pinfunction "2_2") (pintype "passive"))
      (node (ref "R166") (pin "2") (pinfunction "2_2") (pintype "passive"))
    )
    (net (code "83") (name "Net-(R161-Pad2)") (class "Default")
      (node (ref "R161") (pin "2") (pinfunction "2_2") (pintype "passive"))
      (node (ref "R167") (pin "2") (pinfunction "2_2") (pintype "passive"))
    )
    (net (code "84") (name "Net-(R162-Pad2)") (class "Default")
      (node (ref "R162") (pin "2") (pinfunction "2_2") (pintype "passive"))
      (node (ref "R168") (pin "2") (pinfunction "2_2") (pintype "passive"))
    )
    (net (code "85") (name "Net-(R163-Pad1)") (class "Default")
      (node (ref "R163") (pin "1") (pinfunction "1_1") (pintype "passive"))
      (node (ref "R169") (pin "2") (pinfunction "2_2") (pintype "passive"))
    )
    (net (code "86") (name "Net-(R164-Pad1)") (class "Default")
      (node (ref "R164") (pin "1") (pinfunction "1_1") (pintype "passive"))
      (node (ref "R170") (pin "2") (pinfunction "2_2") (pintype "passive"))
    )
    (net (code "87") (name "Net-(R165-Pad1)") (class "Default")
      (node (ref "R165") (pin "1") (pinfunction "1_1") (pintype "passive"))
      (node (ref "R171") (pin "2") (pinfunction "2_2") (pintype "passive"))
    )
    (net (code "88") (name "Net-(R166-Pad1)") (class "Default")
      (node (ref "R166") (pin "1") (pinfunction "1_1") (pintype "passive"))
      (node (ref "R172") (pin "2") (pinfunction "2_2") (pintype "passive"))
    )
    (net (code "89") (name "Net-(R167-Pad1)") (class "Default")
      (node (ref "R167") (pin "1") (pinfunction "1_1") (pintype "passive"))
      (node (ref "R173") (pin "2") (pinfunction "2_2") (pintype "passive"))
    )
    (net (code "90") (name "Net-(R168-Pad1)") (class "Default")
      (node (ref "R168") (pin "1") (pinfunction "1_1") (pintype "passive"))
      (node (ref "R174") (pin "2") (pinfunction "2_2") (pintype "passive"))
    )
    (net (code "91") (name "Net-(R169-Pad1)") (class "Default")
      (node (ref "R169") (pin "1") (pinfunction "1_1") (pintype "passive"))
      (node (ref "R175") (pin "2") (pinfunction "2_2") (pintype "passive"))
    )
    (net (code "92") (name "Net-(R170-Pad1)") (class "Default")
      (node (ref "R170") (pin "1") (pinfunction "1_1") (pintype "passive"))
      (node (ref "R176") (pin "2") (pinfunction "2_2") (pintype "passive"))
    )
    (net (code "93") (name "Net-(R171-Pad1)") (class "Default")
      (node (ref "R171") (pin "1") (pinfunction "1_1") (pintype "passive"))
      (node (ref "R177") (pin "2") (pinfunction "2_2") (pintype "passive"))
    )
    (net (code "94") (name "Net-(R172-Pad1)") (class "Default")
      (node (ref "R172") (pin "1") (pinfunction "1_1") (pintype "passive"))
      (node (ref "R178") (pin "2") (pinfunction "2_2") (pintype "passive"))
    )
    (net (code "95") (name "Net-(R173-Pad1)") (class "Default")
      (node (ref "R173") (pin "1") (pinfunction "1_1") (pintype "passive"))
      (node (ref "R179") (pin "2") (pinfunction "2_2") (pintype "passive"))
    )
    (net (code "96") (name "Net-(R174-Pad1)") (class "Default")
      (node (ref "R174") (pin "1") (pinfunction "1_1") (pintype "passive"))
      (node (ref "R180") (pin "2") (pinfunction "2_2") (pintype "passive"))
    )
  )
)
